# OSSI-1_Beacon_1.net
KiCad netlist of a schematic drawn in Altium Designer
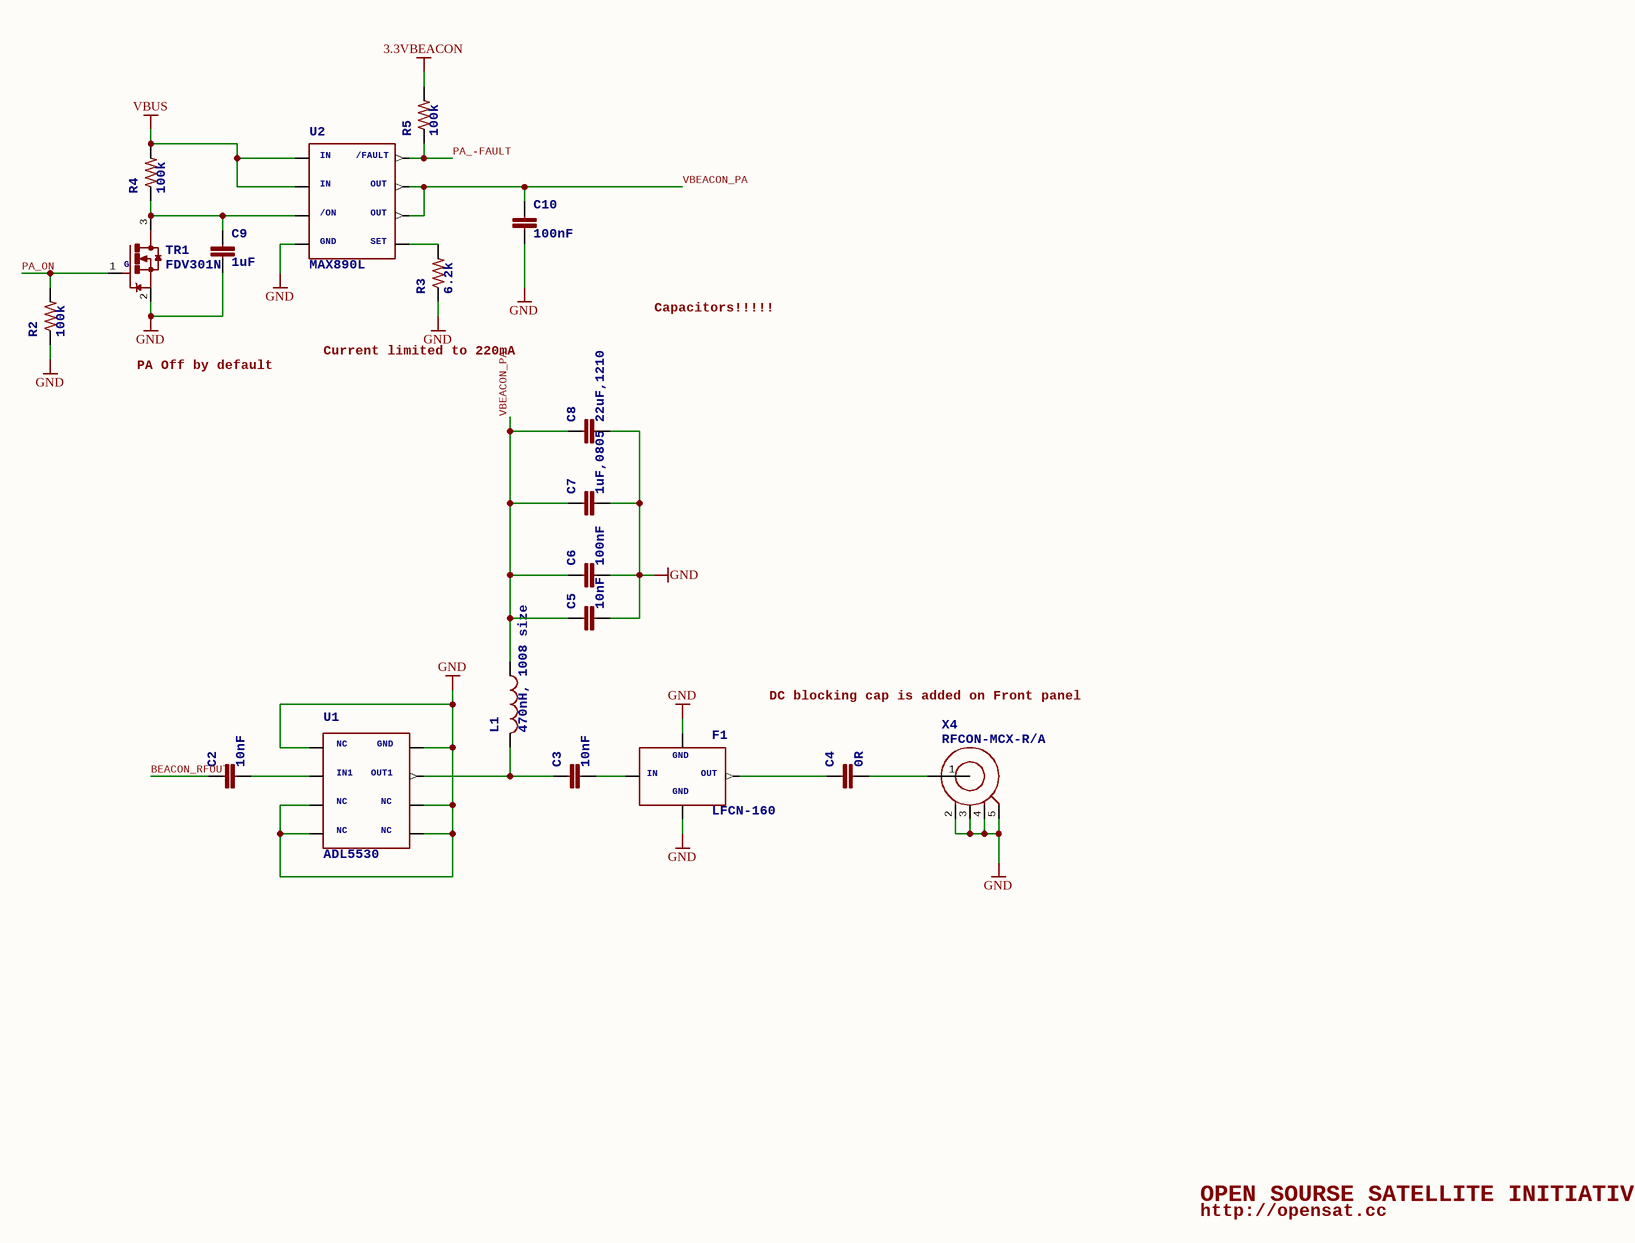
[diagram p0: OSSI-1 Beacon_1.SchDoc]

(export (version "E")
  (design (tool "Eeschema 10.0.6"))
  (components
    (comp (ref "C2")
      (value "10nF")
      (footprint "C0603(1608)")
      (fields (field (name ">NAME") "C2") (field (name ">VALUE") "10nF"))
      (libsource (lib "OSSI") (part "C0603(1608)"))
    )
    (comp (ref "C3")
      (value "10nF")
      (footprint "C0603(1608)")
      (fields (field (name ">NAME") "C3") (field (name ">VALUE") "10nF"))
      (libsource (lib "OSSI") (part "C0603(1608)"))
    )
    (comp (ref "C4")
      (value "0R")
      (footprint "C0603(1608)")
      (fields (field (name ">NAME") "C4") (field (name ">VALUE") "0R"))
      (libsource (lib "OSSI") (part "C0603(1608)"))
    )
    (comp (ref "C5")
      (value "10nF")
      (footprint "C0603(1608)")
      (fields (field (name ">NAME") "C5") (field (name ">VALUE") "10nF"))
      (libsource (lib "OSSI") (part "C0603(1608)"))
    )
    (comp (ref "C6")
      (value "100nF")
      (footprint "C0603(1608)")
      (fields (field (name ">NAME") "C6") (field (name ">VALUE") "100nF"))
      (libsource (lib "OSSI") (part "C0603(1608)"))
    )
    (comp (ref "C7")
      (value "1uF,0805")
      (footprint "C0805(2012)")
      (fields (field (name ">NAME") "C7") (field (name ">VALUE") "1uF,0805"))
      (libsource (lib "OSSI") (part "C0805(2012)"))
    )
    (comp (ref "C8")
      (value "22uF,1210")
      (footprint "C1210-GCM32")
      (fields (field (name ">NAME") "C8") (field (name ">VALUE") "22uF,1210"))
      (libsource (lib "OSSI") (part "C1210(3225)-GCM32"))
    )
    (comp (ref "C9")
      (value "1uF")
      (footprint "C0603(1608)")
      (fields (field (name ">NAME") "C9") (field (name ">VALUE") "1uF"))
      (libsource (lib "") (part "C0603(1608)_1"))
    )
    (comp (ref "C10")
      (value "100nF")
      (footprint "C0603(1608)")
      (fields (field (name ">NAME") "C10") (field (name ">VALUE") "100nF"))
      (libsource (lib "") (part "C0603(1608)_1"))
    )
    (comp (ref "F1")
      (value "LFCN-160")
      (footprint "LFCN")
      (fields
        (field (name "IN") "IN")
        (field (name "OUT") "OUT")
        (field (name "GND") "GND")
        (field (name "GND_1") "GND")
        (field (name ">NAME") "F1")
        (field (name ">VALUE") "LFCN-160")
      )
      (libsource (lib "OSSI") (part "LFCN-160"))
    )
    (comp (ref "L1")
      (value "470nH, 1008 size")
      (footprint "L1008(2520)")
      (fields (field (name ">NAME") "L1") (field (name ">VALUE") "470nH, 1008 size"))
      (libsource (lib "OSSI") (part "L1008(2502)"))
    )
    (comp (ref "R2")
      (value "100k")
      (footprint "R0603(1608)")
      (fields (field (name ">NAME") "R2") (field (name ">VALUE") "100k"))
      (libsource (lib "OSSI") (part "R0603(1608)"))
    )
    (comp (ref "R3")
      (value "6.2k")
      (footprint "R0603(1608)")
      (fields (field (name ">NAME") "R3") (field (name ">VALUE") "6.2k"))
      (libsource (lib "OSSI") (part "R0603(1608)"))
    )
    (comp (ref "R4")
      (value "100k")
      (footprint "R0603(1608)")
      (fields (field (name ">NAME") "R4") (field (name ">VALUE") "100k"))
      (libsource (lib "OSSI") (part "R0603(1608)"))
    )
    (comp (ref "R5")
      (value "100k")
      (footprint "R0603(1608)")
      (fields (field (name ">NAME") "R5") (field (name ">VALUE") "100k"))
      (libsource (lib "OSSI") (part "R0603(1608)"))
    )
    (comp (ref "TR1")
      (value "FDV301N")
      (footprint "SOT23")
      (description "FDV301N Digital N channel - FET / Rdson = 5 Ohm / Vgs = 0.7~1.06V / Ids = 220mA")
      (fields (field (name "G") "G") (field (name ">NAME") "TR1") (field (name ">VALUE") "FDV301N"))
      (libsource (lib "OSSI") (part "FDV301N"))
    )
    (comp (ref "U1")
      (value "ADL5530")
      (footprint "LFCSP8_CP")
      (fields
        (field (name ">NAME") "U1")
        (field (name ">VALUE") "ADL5530")
        (field (name "NC") "NC")
        (field (name "IN1") "IN1")
        (field (name "NC_1") "NC")
        (field (name "NC_2") "NC")
        (field (name "GND") "GND")
        (field (name "OUT1") "OUT1")
        (field (name "NC_3") "NC")
        (field (name "NC_4") "NC")
      )
      (libsource (lib "OSSI") (part "ADL5530"))
    )
    (comp (ref "U2")
      (value "MAX890L")
      (footprint "SO8")
      (fields
        (field (name "IN") "IN")
        (field (name "IN_1") "IN")
        (field (name "/ON") "/ON")
        (field (name "GND") "GND")
        (field (name "SET") "SET")
        (field (name "OUT") "OUT")
        (field (name "OUT_1") "OUT")
        (field (name "/FAULT") "/FAULT")
        (field (name ">NAME") "U2")
        (field (name ">VALUE") "MAX890L")
      )
      (libsource (lib "OSSI") (part "MAX890L"))
    )
    (comp (ref "X4")
      (value "RFCON-MCX-R/A")
      (footprint "MCX-R/A")
      (description "RF Connectors")
      (fields (field (name ">NAME") "X4") (field (name ">VALUE") "RFCON-MCX-R/A"))
      (libsource (lib "OSSI") (part "RFCON-MCX-R/A"))
    )
  )
  (nets
    (net (code "1") (name "/BEACON_RFOUT") (class "Default")
      (node (ref "C2") (pin "1") (pinfunction "1_1") (pintype "passive"))
    )
    (net (code "2") (name "/PA_-FAULT") (class "Default")
      (node (ref "R5") (pin "1") (pinfunction "1_1") (pintype "passive"))
      (node (ref "U2") (pin "8") (pinfunction "P$8_8") (pintype "output"))
    )
    (net (code "3") (name "/PA_ON") (class "Default")
      (node (ref "R2") (pin "2") (pinfunction "2_2") (pintype "passive"))
      (node (ref "TR1") (pin "1") (pinfunction "G_1") (pintype "passive"))
    )
    (net (code "4") (name "/VBEACON_PA") (class "Default")
      (node (ref "C10") (pin "1") (pinfunction "1_1") (pintype "passive"))
      (node (ref "C5") (pin "1") (pinfunction "1_1") (pintype "passive"))
      (node (ref "C6") (pin "1") (pinfunction "1_1") (pintype "passive"))
      (node (ref "C7") (pin "1") (pinfunction "1_1") (pintype "passive"))
      (node (ref "C8") (pin "P$1") (pinfunction "1_P$1") (pintype "passive"))
      (node (ref "L1") (pin "P$1") (pinfunction "1_P$1") (pintype "passive"))
      (node (ref "U2") (pin "6") (pinfunction "P$6_6") (pintype "output"))
      (node (ref "U2") (pin "7") (pinfunction "P$7_7") (pintype "output"))
    )
    (net (code "5") (name "3.3VBEACON") (class "Default")
      (node (ref "R5") (pin "2") (pinfunction "2_2") (pintype "passive"))
    )
    (net (code "6") (name "GND") (class "Default")
      (node (ref "C10") (pin "2") (pinfunction "2_2") (pintype "passive"))
      (node (ref "C5") (pin "2") (pinfunction "2_2") (pintype "passive"))
      (node (ref "C6") (pin "2") (pinfunction "2_2") (pintype "passive"))
      (node (ref "C7") (pin "2") (pinfunction "2_2") (pintype "passive"))
      (node (ref "C8") (pin "P$2") (pinfunction "2_P$2") (pintype "passive"))
      (node (ref "C9") (pin "2") (pinfunction "2_2") (pintype "passive"))
      (node (ref "F1") (pin "2") (pinfunction "P$2_2") (pintype "power_in"))
      (node (ref "F1") (pin "4") (pinfunction "P$4_4") (pintype "power_in"))
      (node (ref "R2") (pin "1") (pinfunction "1_1") (pintype "passive"))
      (node (ref "R3") (pin "1") (pinfunction "1_1") (pintype "passive"))
      (node (ref "TR1") (pin "2") (pinfunction "S_2") (pintype "passive"))
      (node (ref "U1") (pin "1") (pinfunction "1_1") (pintype "passive"))
      (node (ref "U1") (pin "3") (pinfunction "3_3") (pintype "passive"))
      (node (ref "U1") (pin "4") (pinfunction "4_4") (pintype "passive"))
      (node (ref "U1") (pin "5") (pinfunction "5_5") (pintype "passive"))
      (node (ref "U1") (pin "6") (pinfunction "6_6") (pintype "passive"))
      (node (ref "U1") (pin "8") (pinfunction "8_8") (pintype "power_in"))
      (node (ref "U2") (pin "4") (pinfunction "P$4_4") (pintype "power_in"))
      (node (ref "X4") (pin "2") (pinfunction "2_2") (pintype "open_emitter"))
      (node (ref "X4") (pin "3") (pinfunction "3_3") (pintype "open_emitter"))
      (node (ref "X4") (pin "4") (pinfunction "4_4") (pintype "open_emitter"))
      (node (ref "X4") (pin "5") (pinfunction "5_5") (pintype "open_emitter"))
    )
    (net (code "7") (name "Net-(C2-Pad2)") (class "Default")
      (node (ref "C2") (pin "2") (pinfunction "2_2") (pintype "passive"))
      (node (ref "U1") (pin "2") (pinfunction "2_2") (pintype "passive"))
    )
    (net (code "8") (name "Net-(C4-Pad2)") (class "Default")
      (node (ref "C4") (pin "2") (pinfunction "2_2") (pintype "passive"))
      (node (ref "X4") (pin "1") (pinfunction "1_1") (pintype "passive"))
    )
    (net (code "9") (name "Net-(F1-P$1)") (class "Default")
      (node (ref "C3") (pin "2") (pinfunction "2_2") (pintype "passive"))
      (node (ref "F1") (pin "1") (pinfunction "P$1_1") (pintype "passive"))
    )
    (net (code "10") (name "Net-(F1-P$3)") (class "Default")
      (node (ref "C4") (pin "1") (pinfunction "1_1") (pintype "passive"))
      (node (ref "F1") (pin "3") (pinfunction "P$3_3") (pintype "output"))
    )
    (net (code "11") (name "Net-(L1-2)") (class "Default")
      (node (ref "C3") (pin "1") (pinfunction "1_1") (pintype "passive"))
      (node (ref "L1") (pin "P$2") (pinfunction "2_P$2") (pintype "passive"))
      (node (ref "U1") (pin "7") (pinfunction "7_7") (pintype "output"))
    )
    (net (code "12") (name "Net-(TR1-D)") (class "Default")
      (node (ref "C9") (pin "1") (pinfunction "1_1") (pintype "passive"))
      (node (ref "R4") (pin "1") (pinfunction "1_1") (pintype "passive"))
      (node (ref "TR1") (pin "3") (pinfunction "D_3") (pintype "passive"))
      (node (ref "U2") (pin "3") (pinfunction "P$3_3") (pintype "passive"))
    )
    (net (code "13") (name "Net-(U2-P$5)") (class "Default")
      (node (ref "R3") (pin "2") (pinfunction "2_2") (pintype "passive"))
      (node (ref "U2") (pin "5") (pinfunction "P$5_5") (pintype "passive"))
    )
    (net (code "14") (name "VBUS") (class "Default")
      (node (ref "R4") (pin "2") (pinfunction "2_2") (pintype "passive"))
      (node (ref "U2") (pin "1") (pinfunction "P$1_1") (pintype "passive"))
      (node (ref "U2") (pin "2") (pinfunction "P$2_2") (pintype "passive"))
    )
  )
)
